# PCI_short_card_universal_-_32_BIT-5.net
KiCad netlist of a schematic drawn in Altium Designer
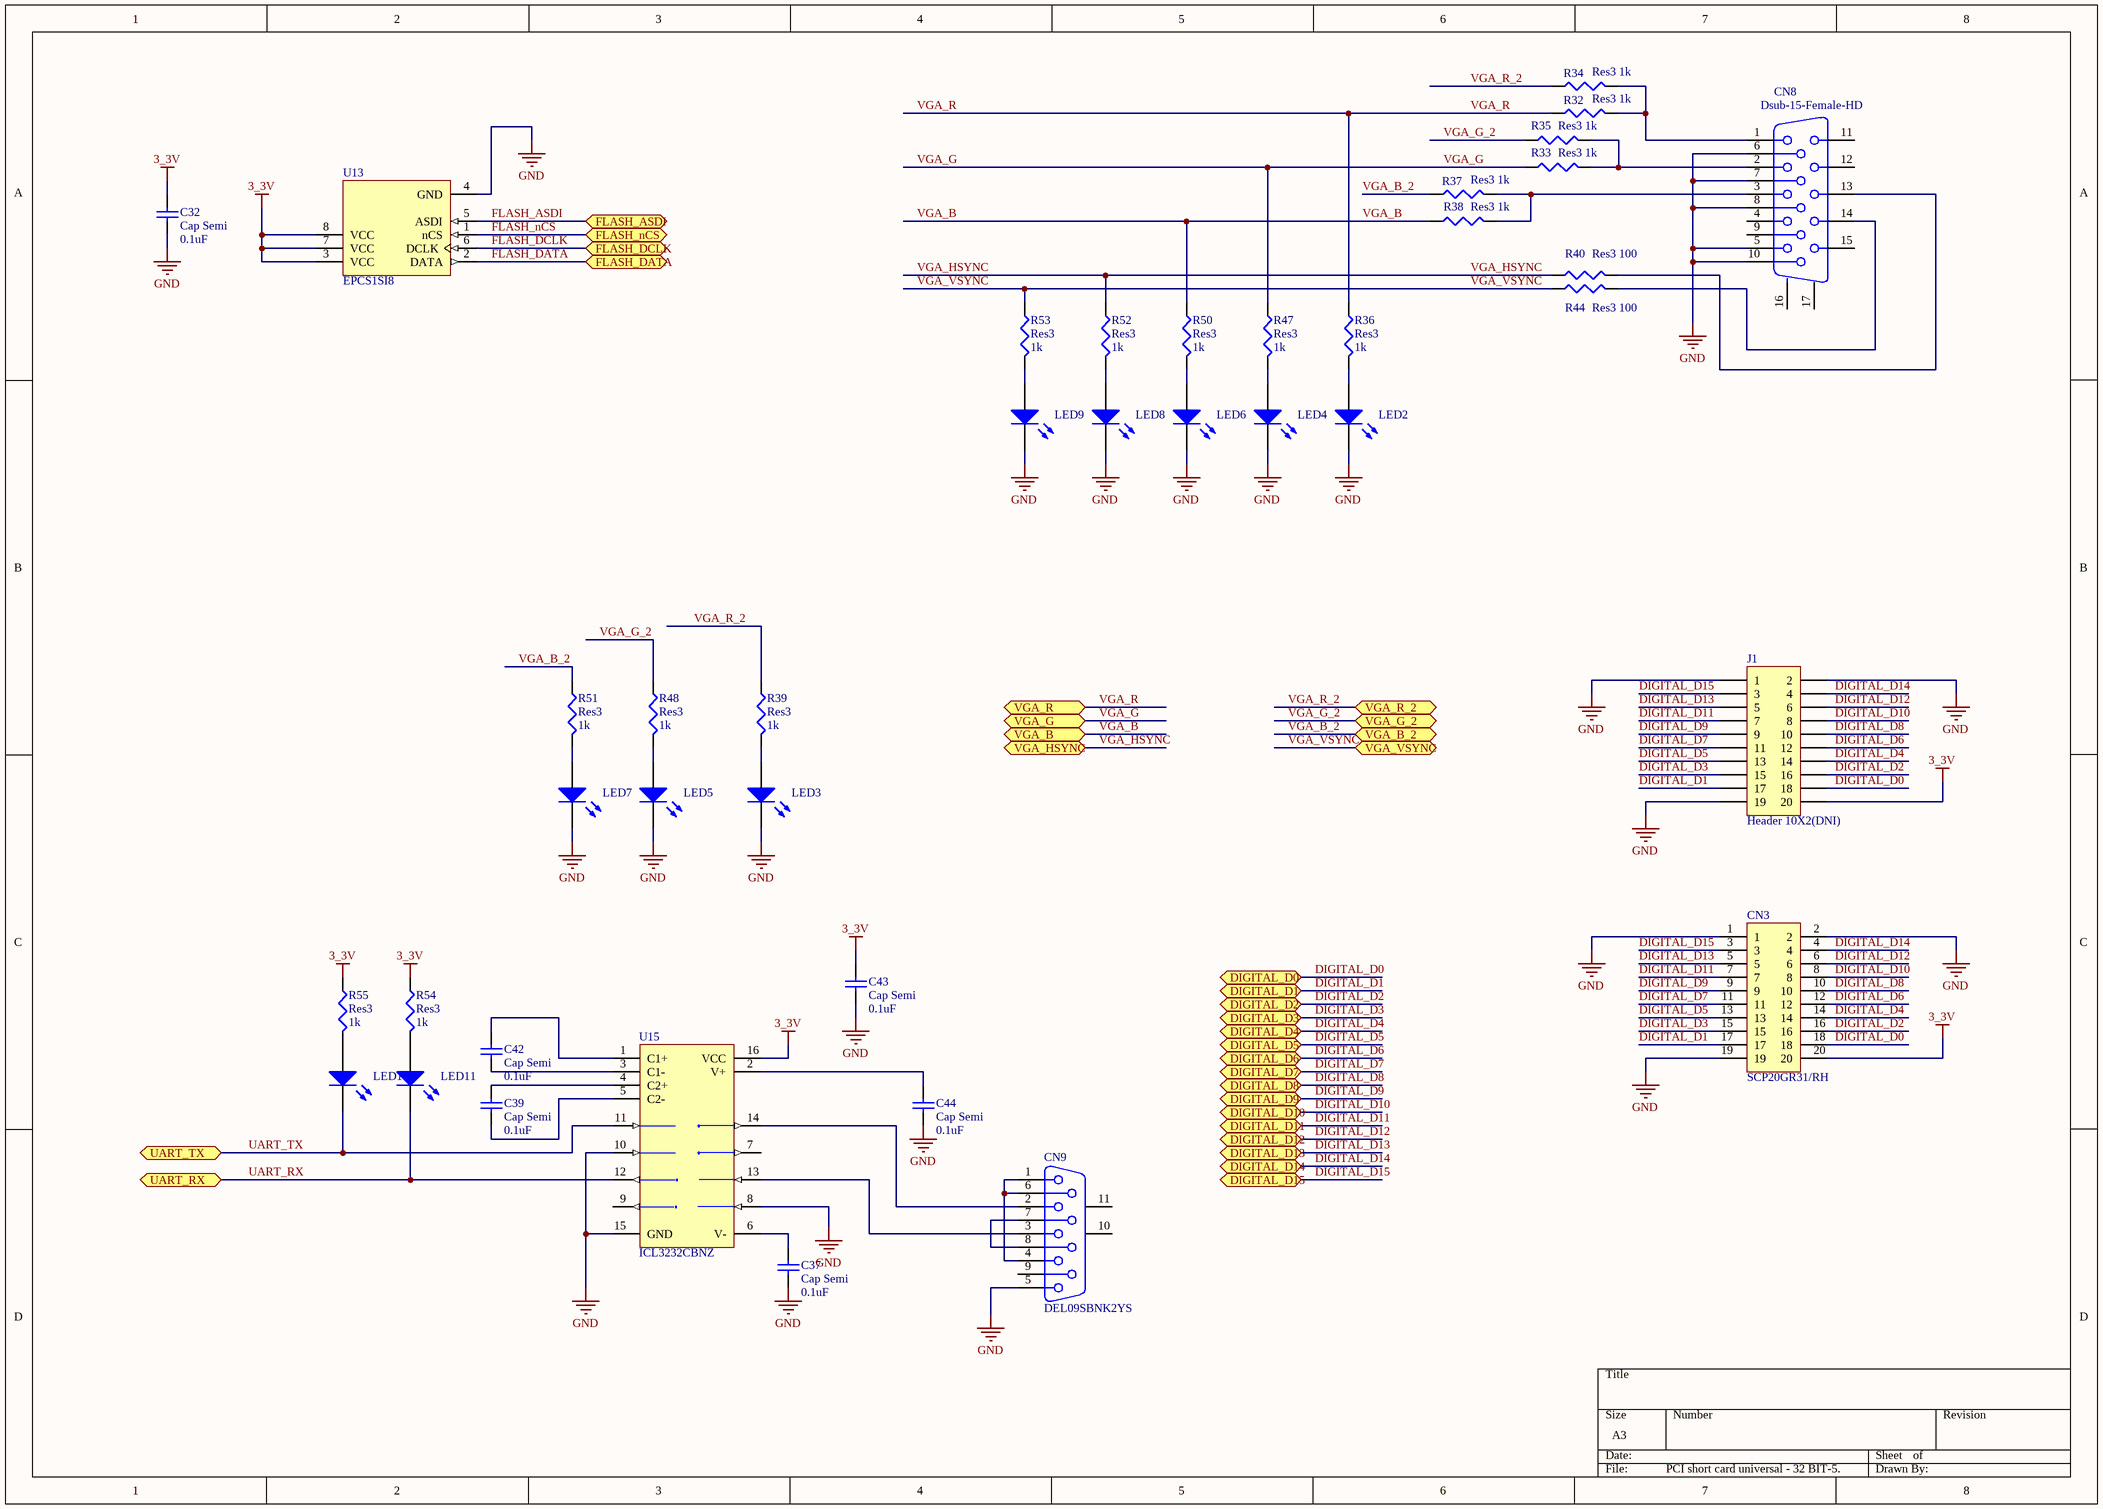
[diagram p0: PCI short card universal - 32 BIT-5.schdoc]

(export (version "E")
  (design (tool "Eeschema 10.0.6"))
  (components
    (comp (ref "C32")
      (value "Cap Semi")
      (footprint "RESC1608N")
      (description "Capacitor (Semiconductor SIM Model)")
      (fields (field (name "ALTIUM_VALUE") "0.1uF") (field (name "PUBLISHER") "Altium Limited"))
      (libsource (lib "Miscellaneous Devices") (part "Cap Semi"))
    )
    (comp (ref "C37")
      (value "Cap Semi")
      (footprint "RESC1608N")
      (description "Capacitor (Semiconductor SIM Model)")
      (fields (field (name "ALTIUM_VALUE") "0.1uF") (field (name "PUBLISHER") "Altium Limited"))
      (libsource (lib "Miscellaneous Devices") (part "Cap Semi"))
    )
    (comp (ref "C39")
      (value "Cap Semi")
      (footprint "RESC1608N")
      (description "Capacitor (Semiconductor SIM Model)")
      (fields (field (name "ALTIUM_VALUE") "0.1uF") (field (name "PUBLISHER") "Altium Limited"))
      (libsource (lib "Miscellaneous Devices") (part "Cap Semi"))
    )
    (comp (ref "C42")
      (value "Cap Semi")
      (footprint "RESC1608N")
      (description "Capacitor (Semiconductor SIM Model)")
      (fields (field (name "ALTIUM_VALUE") "0.1uF") (field (name "PUBLISHER") "Altium Limited"))
      (libsource (lib "Miscellaneous Devices") (part "Cap Semi"))
    )
    (comp (ref "C43")
      (value "Cap Semi")
      (footprint "RESC1608N")
      (description "Capacitor (Semiconductor SIM Model)")
      (fields (field (name "ALTIUM_VALUE") "0.1uF") (field (name "PUBLISHER") "Altium Limited"))
      (libsource (lib "Miscellaneous Devices") (part "Cap Semi"))
    )
    (comp (ref "C44")
      (value "Cap Semi")
      (footprint "RESC1608N")
      (description "Capacitor (Semiconductor SIM Model)")
      (fields (field (name "ALTIUM_VALUE") "0.1uF") (field (name "PUBLISHER") "Altium Limited"))
      (libsource (lib "Miscellaneous Devices") (part "Cap Semi"))
    )
    (comp (ref "CN3")
      (value "SCP20GR31/RH")
      (footprint "SCP20GR31/RH")
      (description "GTK")
      (libsource (lib "Schlib1") (part "SCP20GR31/RH"))
    )
    (comp (ref "CN8")
      (value "Dsub-15-Female-HD")
      (footprint "MyPCBLib:DB15-VGA-Female")
      (description "Dsub-15 High density VGA Female connetor")
      (fields (field (name "MANUFACTURER") "Generic Components") (field (name "PUBLISHER") "Altium Limited"))
      (libsource (lib "Altium Nanoboard Project") (part "Dsub-15-Female-HD"))
    )
    (comp (ref "CN9")
      (value "DEL09SBNK2YS")
      (footprint "DSUB1.385-2H9")
      (description "GTK")
      (fields (field (name "PUBLISHER") "Altium Limited"))
      (libsource (lib "Miscellaneous Connectors") (part "D Connector 9"))
    )
    (comp (ref "J1")
      (value "Header 10X2(DNI)")
      (footprint "HDR2X10")
      (description "Header, 10-Pin, Dual row")
      (fields (field (name "PUBLISHER") "Altium Limited"))
      (libsource (lib "Miscellaneous Connectors") (part "Header 10X2"))
    )
    (comp (ref "LED2")
      (value "LED2")
      (footprint "LED3.2X1.6X1.1")
      (description "OASISTEK (TO-3216BC-MAE)")
      (fields (field (name "PUBLISHER") "Altium Limited"))
      (libsource (lib "Miscellaneous Devices") (part "LED2"))
    )
    (comp (ref "LED3")
      (value "LED2")
      (footprint "LED3.2X1.6X1.1")
      (description "OASISTEK (TO-3216BC-MAE)")
      (fields (field (name "PUBLISHER") "Altium Limited"))
      (libsource (lib "Miscellaneous Devices") (part "LED2"))
    )
    (comp (ref "LED4")
      (value "LED2")
      (footprint "LED3.2X1.6X1.1")
      (description "OASISTEK (TO-3216BC-MAE)")
      (fields (field (name "PUBLISHER") "Altium Limited"))
      (libsource (lib "Miscellaneous Devices") (part "LED2"))
    )
    (comp (ref "LED5")
      (value "LED2")
      (footprint "LED3.2X1.6X1.1")
      (description "OASISTEK (TO-3216BC-MAE)")
      (fields (field (name "PUBLISHER") "Altium Limited"))
      (libsource (lib "Miscellaneous Devices") (part "LED2"))
    )
    (comp (ref "LED6")
      (value "LED2")
      (footprint "LED3.2X1.6X1.1")
      (description "OASISTEK (TO-3216BC-MAE)")
      (fields (field (name "PUBLISHER") "Altium Limited"))
      (libsource (lib "Miscellaneous Devices") (part "LED2"))
    )
    (comp (ref "LED7")
      (value "LED2")
      (footprint "LED3.2X1.6X1.1")
      (description "OASISTEK (TO-3216BC-MAE)")
      (fields (field (name "PUBLISHER") "Altium Limited"))
      (libsource (lib "Miscellaneous Devices") (part "LED2"))
    )
    (comp (ref "LED8")
      (value "LED2")
      (footprint "LED3.2X1.6X1.1")
      (description "OASISTEK (TO-3216BC-MAE)")
      (fields (field (name "PUBLISHER") "Altium Limited"))
      (libsource (lib "Miscellaneous Devices") (part "LED2"))
    )
    (comp (ref "LED9")
      (value "LED2")
      (footprint "LED3.2X1.6X1.1")
      (description "OASISTEK (TO-3216BC-MAE)")
      (fields (field (name "PUBLISHER") "Altium Limited"))
      (libsource (lib "Miscellaneous Devices") (part "LED2"))
    )
    (comp (ref "LED10")
      (value "LED2")
      (footprint "LED3.2X1.6X1.1")
      (description "Typical RED, GREEN, YELLOW, AMBER GaAs LED")
      (fields (field (name "PUBLISHER") "Altium Limited"))
      (libsource (lib "Miscellaneous Devices") (part "LED2"))
    )
    (comp (ref "LED11")
      (value "LED2")
      (footprint "LED3.2X1.6X1.1")
      (description "Typical RED, GREEN, YELLOW, AMBER GaAs LED")
      (fields (field (name "PUBLISHER") "Altium Limited"))
      (libsource (lib "Miscellaneous Devices") (part "LED2"))
    )
    (comp (ref "R32")
      (value "Res3")
      (footprint "RESC1608N")
      (description "Resistor")
      (fields (field (name "ALTIUM_VALUE") "1k") (field (name "PUBLISHER") "Altium Limited"))
      (libsource (lib "Miscellaneous Devices") (part "Res3"))
    )
    (comp (ref "R33")
      (value "Res3")
      (footprint "RESC1608N")
      (description "Resistor")
      (fields (field (name "ALTIUM_VALUE") "1k") (field (name "PUBLISHER") "Altium Limited"))
      (libsource (lib "Miscellaneous Devices") (part "Res3"))
    )
    (comp (ref "R34")
      (value "Res3")
      (footprint "RESC1608N")
      (description "Resistor")
      (fields (field (name "ALTIUM_VALUE") "1k") (field (name "PUBLISHER") "Altium Limited"))
      (libsource (lib "Miscellaneous Devices") (part "Res3"))
    )
    (comp (ref "R35")
      (value "Res3")
      (footprint "RESC1608N")
      (description "Resistor")
      (fields (field (name "ALTIUM_VALUE") "1k") (field (name "PUBLISHER") "Altium Limited"))
      (libsource (lib "Miscellaneous Devices") (part "Res3"))
    )
    (comp (ref "R36")
      (value "Res3")
      (footprint "RESC1608N")
      (description "Resistor")
      (fields (field (name "ALTIUM_VALUE") "1k") (field (name "PUBLISHER") "Altium Limited"))
      (libsource (lib "Miscellaneous Devices") (part "Res3"))
    )
    (comp (ref "R37")
      (value "Res3")
      (footprint "RESC1608N")
      (description "Resistor")
      (fields (field (name "ALTIUM_VALUE") "1k") (field (name "PUBLISHER") "Altium Limited"))
      (libsource (lib "Miscellaneous Devices") (part "Res3"))
    )
    (comp (ref "R38")
      (value "Res3")
      (footprint "RESC1608N")
      (description "Resistor")
      (fields (field (name "ALTIUM_VALUE") "1k") (field (name "PUBLISHER") "Altium Limited"))
      (libsource (lib "Miscellaneous Devices") (part "Res3"))
    )
    (comp (ref "R39")
      (value "Res3")
      (footprint "RESC1608N")
      (description "Resistor")
      (fields (field (name "ALTIUM_VALUE") "1k") (field (name "PUBLISHER") "Altium Limited"))
      (libsource (lib "Miscellaneous Devices") (part "Res3"))
    )
    (comp (ref "R40")
      (value "Res3")
      (footprint "RESC1608N")
      (description "Resistor")
      (fields (field (name "ALTIUM_VALUE") "100") (field (name "PUBLISHER") "Altium Limited"))
      (libsource (lib "Miscellaneous Devices") (part "Res3"))
    )
    (comp (ref "R44")
      (value "Res3")
      (footprint "RESC1608N")
      (description "Resistor")
      (fields (field (name "ALTIUM_VALUE") "100") (field (name "PUBLISHER") "Altium Limited"))
      (libsource (lib "Miscellaneous Devices") (part "Res3"))
    )
    (comp (ref "R47")
      (value "Res3")
      (footprint "RESC1608N")
      (description "Resistor")
      (fields (field (name "ALTIUM_VALUE") "1k") (field (name "PUBLISHER") "Altium Limited"))
      (libsource (lib "Miscellaneous Devices") (part "Res3"))
    )
    (comp (ref "R48")
      (value "Res3")
      (footprint "RESC1608N")
      (description "Resistor")
      (fields (field (name "ALTIUM_VALUE") "1k") (field (name "PUBLISHER") "Altium Limited"))
      (libsource (lib "Miscellaneous Devices") (part "Res3"))
    )
    (comp (ref "R50")
      (value "Res3")
      (footprint "RESC1608N")
      (description "Resistor")
      (fields (field (name "ALTIUM_VALUE") "1k") (field (name "PUBLISHER") "Altium Limited"))
      (libsource (lib "Miscellaneous Devices") (part "Res3"))
    )
    (comp (ref "R51")
      (value "Res3")
      (footprint "RESC1608N")
      (description "Resistor")
      (fields (field (name "ALTIUM_VALUE") "1k") (field (name "PUBLISHER") "Altium Limited"))
      (libsource (lib "Miscellaneous Devices") (part "Res3"))
    )
    (comp (ref "R52")
      (value "Res3")
      (footprint "RESC1608N")
      (description "Resistor")
      (fields (field (name "ALTIUM_VALUE") "1k") (field (name "PUBLISHER") "Altium Limited"))
      (libsource (lib "Miscellaneous Devices") (part "Res3"))
    )
    (comp (ref "R53")
      (value "Res3")
      (footprint "RESC1608N")
      (description "Resistor")
      (fields (field (name "ALTIUM_VALUE") "1k") (field (name "PUBLISHER") "Altium Limited"))
      (libsource (lib "Miscellaneous Devices") (part "Res3"))
    )
    (comp (ref "R54")
      (value "Res3")
      (footprint "RESC1608N")
      (description "Resistor")
      (fields (field (name "ALTIUM_VALUE") "1k") (field (name "PUBLISHER") "Altium Limited"))
      (libsource (lib "Miscellaneous Devices") (part "Res3"))
    )
    (comp (ref "R55")
      (value "Res3")
      (footprint "RESC1608N")
      (description "Resistor")
      (fields (field (name "ALTIUM_VALUE") "1k") (field (name "PUBLISHER") "Altium Limited"))
      (libsource (lib "Miscellaneous Devices") (part "Res3"))
    )
    (comp (ref "U13")
      (value "EPCS1SI8")
      (footprint "SOIC8_L")
      (fields (field (name "PUBLISHER") "Altium Limited"))
      (libsource (lib "Altera EPCS Configuration Device") (part "EPCS1SI8"))
    )
    (comp (ref "U15")
      (value "ICL3232CBNZ")
      (footprint "NSO16_M")
      (description "INTERSIL")
      (fields (field (name "PUBLISHER") "Altium Limited"))
      (libsource (lib "Maxim Communication Transceiver") (part "MAX3232CSE"))
    )
  )
  (nets
    (net (code "1") (name "/DIGITAL_D0") (class "Default")
      (node (ref "CN3") (pin "18") (pinfunction "18_18") (pintype "passive"))
      (node (ref "J1") (pin "18") (pinfunction "18_18") (pintype "passive"))
    )
    (net (code "2") (name "/DIGITAL_D1") (class "Default")
      (node (ref "CN3") (pin "17") (pinfunction "17_17") (pintype "passive"))
      (node (ref "J1") (pin "17") (pinfunction "17_17") (pintype "passive"))
    )
    (net (code "3") (name "/DIGITAL_D2") (class "Default")
      (node (ref "CN3") (pin "16") (pinfunction "16_16") (pintype "passive"))
      (node (ref "J1") (pin "16") (pinfunction "16_16") (pintype "passive"))
    )
    (net (code "4") (name "/DIGITAL_D3") (class "Default")
      (node (ref "CN3") (pin "15") (pinfunction "15_15") (pintype "passive"))
      (node (ref "J1") (pin "15") (pinfunction "15_15") (pintype "passive"))
    )
    (net (code "5") (name "/DIGITAL_D4") (class "Default")
      (node (ref "CN3") (pin "14") (pinfunction "14_14") (pintype "passive"))
      (node (ref "J1") (pin "14") (pinfunction "14_14") (pintype "passive"))
    )
    (net (code "6") (name "/DIGITAL_D5") (class "Default")
      (node (ref "CN3") (pin "13") (pinfunction "13_13") (pintype "passive"))
      (node (ref "J1") (pin "13") (pinfunction "13_13") (pintype "passive"))
    )
    (net (code "7") (name "/DIGITAL_D6") (class "Default")
      (node (ref "CN3") (pin "12") (pinfunction "12_12") (pintype "passive"))
      (node (ref "J1") (pin "12") (pinfunction "12_12") (pintype "passive"))
    )
    (net (code "8") (name "/DIGITAL_D7") (class "Default")
      (node (ref "CN3") (pin "11") (pinfunction "11_11") (pintype "passive"))
      (node (ref "J1") (pin "11") (pinfunction "11_11") (pintype "passive"))
    )
    (net (code "9") (name "/DIGITAL_D8") (class "Default")
      (node (ref "CN3") (pin "10") (pinfunction "10_10") (pintype "passive"))
      (node (ref "J1") (pin "10") (pinfunction "10_10") (pintype "passive"))
    )
    (net (code "10") (name "/DIGITAL_D9") (class "Default")
      (node (ref "CN3") (pin "9") (pinfunction "9_9") (pintype "passive"))
      (node (ref "J1") (pin "9") (pinfunction "9_9") (pintype "passive"))
    )
    (net (code "11") (name "/DIGITAL_D10") (class "Default")
      (node (ref "CN3") (pin "8") (pinfunction "8_8") (pintype "passive"))
      (node (ref "J1") (pin "8") (pinfunction "8_8") (pintype "passive"))
    )
    (net (code "12") (name "/DIGITAL_D11") (class "Default")
      (node (ref "CN3") (pin "7") (pinfunction "7_7") (pintype "passive"))
      (node (ref "J1") (pin "7") (pinfunction "7_7") (pintype "passive"))
    )
    (net (code "13") (name "/DIGITAL_D12") (class "Default")
      (node (ref "CN3") (pin "6") (pinfunction "6_6") (pintype "passive"))
      (node (ref "J1") (pin "6") (pinfunction "6_6") (pintype "passive"))
    )
    (net (code "14") (name "/DIGITAL_D13") (class "Default")
      (node (ref "CN3") (pin "5") (pinfunction "5_5") (pintype "passive"))
      (node (ref "J1") (pin "5") (pinfunction "5_5") (pintype "passive"))
    )
    (net (code "15") (name "/DIGITAL_D14") (class "Default")
      (node (ref "CN3") (pin "4") (pinfunction "4_4") (pintype "passive"))
      (node (ref "J1") (pin "4") (pinfunction "4_4") (pintype "passive"))
    )
    (net (code "16") (name "/DIGITAL_D15") (class "Default")
      (node (ref "CN3") (pin "3") (pinfunction "3_3") (pintype "passive"))
      (node (ref "J1") (pin "3") (pinfunction "3_3") (pintype "passive"))
    )
    (net (code "17") (name "/FLASH_ASDI") (class "Default")
      (node (ref "U13") (pin "5") (pinfunction "ASDI_5") (pintype "input"))
    )
    (net (code "18") (name "/FLASH_DATA") (class "Default")
      (node (ref "U13") (pin "2") (pinfunction "DATA_2") (pintype "output"))
    )
    (net (code "19") (name "/FLASH_DCLK") (class "Default")
      (node (ref "U13") (pin "6") (pinfunction "DCLK_6") (pintype "input"))
    )
    (net (code "20") (name "/FLASH_nCS") (class "Default")
      (node (ref "U13") (pin "1") (pinfunction "nCS_1") (pintype "input"))
    )
    (net (code "21") (name "/UART_RX") (class "Default")
      (node (ref "LED11") (pin "2") (pinfunction "K_2") (pintype "passive"))
      (node (ref "U15") (pin "12") (pinfunction "R1OUT_12") (pintype "output"))
    )
    (net (code "22") (name "/UART_TX") (class "Default")
      (node (ref "LED10") (pin "2") (pinfunction "K_2") (pintype "passive"))
      (node (ref "U15") (pin "11") (pinfunction "T1IN_11") (pintype "input"))
    )
    (net (code "23") (name "/VGA_B") (class "Default")
      (node (ref "R38") (pin "1") (pinfunction "1_1") (pintype "passive"))
      (node (ref "R50") (pin "1") (pinfunction "1_1") (pintype "passive"))
    )
    (net (code "24") (name "/VGA_B_2") (class "Default")
      (node (ref "R37") (pin "1") (pinfunction "1_1") (pintype "passive"))
      (node (ref "R51") (pin "1") (pinfunction "1_1") (pintype "passive"))
    )
    (net (code "25") (name "/VGA_G") (class "Default")
      (node (ref "R33") (pin "1") (pinfunction "1_1") (pintype "passive"))
      (node (ref "R47") (pin "1") (pinfunction "1_1") (pintype "passive"))
    )
    (net (code "26") (name "/VGA_G_2") (class "Default")
      (node (ref "R35") (pin "1") (pinfunction "1_1") (pintype "passive"))
      (node (ref "R48") (pin "1") (pinfunction "1_1") (pintype "passive"))
    )
    (net (code "27") (name "/VGA_HSYNC") (class "Default")
      (node (ref "R40") (pin "1") (pinfunction "1_1") (pintype "passive"))
      (node (ref "R52") (pin "1") (pinfunction "1_1") (pintype "passive"))
    )
    (net (code "28") (name "/VGA_R") (class "Default")
      (node (ref "R32") (pin "1") (pinfunction "1_1") (pintype "passive"))
      (node (ref "R36") (pin "1") (pinfunction "1_1") (pintype "passive"))
    )
    (net (code "29") (name "/VGA_R_2") (class "Default")
      (node (ref "R34") (pin "1") (pinfunction "1_1") (pintype "passive"))
      (node (ref "R39") (pin "1") (pinfunction "1_1") (pintype "passive"))
    )
    (net (code "30") (name "/VGA_VSYNC") (class "Default")
      (node (ref "R44") (pin "1") (pinfunction "1_1") (pintype "passive"))
      (node (ref "R53") (pin "1") (pinfunction "1_1") (pintype "passive"))
    )
    (net (code "31") (name "3_3V") (class "Default")
      (node (ref "C32") (pin "2") (pinfunction "2_2") (pintype "passive"))
      (node (ref "C43") (pin "2") (pinfunction "2_2") (pintype "passive"))
      (node (ref "CN3") (pin "20") (pinfunction "20_20") (pintype "passive"))
      (node (ref "J1") (pin "20") (pinfunction "20_20") (pintype "passive"))
      (node (ref "R54") (pin "1") (pinfunction "1_1") (pintype "passive"))
      (node (ref "R55") (pin "1") (pinfunction "1_1") (pintype "passive"))
      (node (ref "U13") (pin "3") (pinfunction "VCC_3") (pintype "power_in"))
      (node (ref "U13") (pin "7") (pinfunction "VCC_7") (pintype "power_in"))
      (node (ref "U13") (pin "8") (pinfunction "VCC_8") (pintype "power_in"))
      (node (ref "U15") (pin "16") (pinfunction "VCC_16") (pintype "power_in"))
    )
    (net (code "32") (name "GND") (class "Default")
      (node (ref "C32") (pin "1") (pinfunction "1_1") (pintype "passive"))
      (node (ref "C37") (pin "1") (pinfunction "1_1") (pintype "passive"))
      (node (ref "C43") (pin "1") (pinfunction "1_1") (pintype "passive"))
      (node (ref "C44") (pin "1") (pinfunction "1_1") (pintype "passive"))
      (node (ref "CN3") (pin "1") (pinfunction "1_1") (pintype "passive"))
      (node (ref "CN3") (pin "19") (pinfunction "19_19") (pintype "passive"))
      (node (ref "CN3") (pin "2") (pinfunction "2_2") (pintype "passive"))
      (node (ref "CN8") (pin "10") (pinfunction "10_10") (pintype "power_in"))
      (node (ref "CN8") (pin "5") (pinfunction "5_5") (pintype "power_in"))
      (node (ref "CN8") (pin "6") (pinfunction "6_6") (pintype "power_in"))
      (node (ref "CN8") (pin "7") (pinfunction "7_7") (pintype "power_in"))
      (node (ref "CN8") (pin "8") (pinfunction "8_8") (pintype "power_in"))
      (node (ref "CN9") (pin "5") (pinfunction "5_5") (pintype "passive"))
      (node (ref "J1") (pin "1") (pinfunction "1_1") (pintype "passive"))
      (node (ref "J1") (pin "19") (pinfunction "19_19") (pintype "passive"))
      (node (ref "J1") (pin "2") (pinfunction "2_2") (pintype "passive"))
      (node (ref "LED2") (pin "2") (pinfunction "K_2") (pintype "passive"))
      (node (ref "LED3") (pin "2") (pinfunction "K_2") (pintype "passive"))
      (node (ref "LED4") (pin "2") (pinfunction "K_2") (pintype "passive"))
      (node (ref "LED5") (pin "2") (pinfunction "K_2") (pintype "passive"))
      (node (ref "LED6") (pin "2") (pinfunction "K_2") (pintype "passive"))
      (node (ref "LED7") (pin "2") (pinfunction "K_2") (pintype "passive"))
      (node (ref "LED8") (pin "2") (pinfunction "K_2") (pintype "passive"))
      (node (ref "LED9") (pin "2") (pinfunction "K_2") (pintype "passive"))
      (node (ref "U13") (pin "4") (pinfunction "GND_4") (pintype "power_in"))
      (node (ref "U15") (pin "10") (pinfunction "T2IN_10") (pintype "input"))
      (node (ref "U15") (pin "15") (pinfunction "GND_15") (pintype "power_in"))
      (node (ref "U15") (pin "8") (pinfunction "R2IN_8") (pintype "input"))
    )
    (net (code "33") (name "Net-(CN8-Pad1)") (class "Default")
      (node (ref "CN8") (pin "1") (pinfunction "1_1") (pintype "passive"))
      (node (ref "R32") (pin "2") (pinfunction "2_2") (pintype "passive"))
      (node (ref "R34") (pin "2") (pinfunction "2_2") (pintype "passive"))
    )
    (net (code "34") (name "Net-(CN8-Pad2)") (class "Default")
      (node (ref "CN8") (pin "2") (pinfunction "2_2") (pintype "passive"))
      (node (ref "R33") (pin "2") (pinfunction "2_2") (pintype "passive"))
      (node (ref "R35") (pin "2") (pinfunction "2_2") (pintype "passive"))
    )
    (net (code "35") (name "Net-(CN8-Pad3)") (class "Default")
      (node (ref "CN8") (pin "3") (pinfunction "3_3") (pintype "passive"))
      (node (ref "R37") (pin "2") (pinfunction "2_2") (pintype "passive"))
      (node (ref "R38") (pin "2") (pinfunction "2_2") (pintype "passive"))
    )
    (net (code "36") (name "Net-(CN8-Pad13)") (class "Default")
      (node (ref "CN8") (pin "13") (pinfunction "13_13") (pintype "passive"))
      (node (ref "R40") (pin "2") (pinfunction "2_2") (pintype "passive"))
    )
    (net (code "37") (name "Net-(CN8-Pad14)") (class "Default")
      (node (ref "CN8") (pin "14") (pinfunction "14_14") (pintype "passive"))
      (node (ref "R44") (pin "2") (pinfunction "2_2") (pintype "passive"))
    )
    (net (code "38") (name "Net-(CN9-Pad1)") (class "Default")
      (node (ref "CN9") (pin "1") (pinfunction "1_1") (pintype "passive"))
      (node (ref "CN9") (pin "4") (pinfunction "4_4") (pintype "passive"))
      (node (ref "CN9") (pin "6") (pinfunction "6_6") (pintype "passive"))
    )
    (net (code "39") (name "Net-(CN9-Pad7)") (class "Default")
      (node (ref "CN9") (pin "7") (pinfunction "7_7") (pintype "passive"))
      (node (ref "CN9") (pin "8") (pinfunction "8_8") (pintype "passive"))
    )
    (net (code "40") (name "Net-(LED2-A)") (class "Default")
      (node (ref "LED2") (pin "1") (pinfunction "A_1") (pintype "passive"))
      (node (ref "R36") (pin "2") (pinfunction "2_2") (pintype "passive"))
    )
    (net (code "41") (name "Net-(LED3-A)") (class "Default")
      (node (ref "LED3") (pin "1") (pinfunction "A_1") (pintype "passive"))
      (node (ref "R39") (pin "2") (pinfunction "2_2") (pintype "passive"))
    )
    (net (code "42") (name "Net-(LED4-A)") (class "Default")
      (node (ref "LED4") (pin "1") (pinfunction "A_1") (pintype "passive"))
      (node (ref "R47") (pin "2") (pinfunction "2_2") (pintype "passive"))
    )
    (net (code "43") (name "Net-(LED5-A)") (class "Default")
      (node (ref "LED5") (pin "1") (pinfunction "A_1") (pintype "passive"))
      (node (ref "R48") (pin "2") (pinfunction "2_2") (pintype "passive"))
    )
    (net (code "44") (name "Net-(LED6-A)") (class "Default")
      (node (ref "LED6") (pin "1") (pinfunction "A_1") (pintype "passive"))
      (node (ref "R50") (pin "2") (pinfunction "2_2") (pintype "passive"))
    )
    (net (code "45") (name "Net-(LED7-A)") (class "Default")
      (node (ref "LED7") (pin "1") (pinfunction "A_1") (pintype "passive"))
      (node (ref "R51") (pin "2") (pinfunction "2_2") (pintype "passive"))
    )
    (net (code "46") (name "Net-(LED8-A)") (class "Default")
      (node (ref "LED8") (pin "1") (pinfunction "A_1") (pintype "passive"))
      (node (ref "R52") (pin "2") (pinfunction "2_2") (pintype "passive"))
    )
    (net (code "47") (name "Net-(LED9-A)") (class "Default")
      (node (ref "LED9") (pin "1") (pinfunction "A_1") (pintype "passive"))
      (node (ref "R53") (pin "2") (pinfunction "2_2") (pintype "passive"))
    )
    (net (code "48") (name "Net-(LED10-A)") (class "Default")
      (node (ref "LED10") (pin "1") (pinfunction "A_1") (pintype "passive"))
      (node (ref "R55") (pin "2") (pinfunction "2_2") (pintype "passive"))
    )
    (net (code "49") (name "Net-(LED11-A)") (class "Default")
      (node (ref "LED11") (pin "1") (pinfunction "A_1") (pintype "passive"))
      (node (ref "R54") (pin "2") (pinfunction "2_2") (pintype "passive"))
    )
    (net (code "50") (name "Net-(U15-C1+)") (class "Default")
      (node (ref "C42") (pin "2") (pinfunction "2_2") (pintype "passive"))
      (node (ref "U15") (pin "1") (pinfunction "C1+_1") (pintype "passive"))
    )
    (net (code "51") (name "Net-(U15-C1-)") (class "Default")
      (node (ref "C42") (pin "1") (pinfunction "1_1") (pintype "passive"))
      (node (ref "U15") (pin "3") (pinfunction "C1-_3") (pintype "passive"))
    )
    (net (code "52") (name "Net-(U15-C2+)") (class "Default")
      (node (ref "C39") (pin "2") (pinfunction "2_2") (pintype "passive"))
      (node (ref "U15") (pin "4") (pinfunction "C2+_4") (pintype "passive"))
    )
    (net (code "53") (name "Net-(U15-C2-)") (class "Default")
      (node (ref "C39") (pin "1") (pinfunction "1_1") (pintype "passive"))
      (node (ref "U15") (pin "5") (pinfunction "C2-_5") (pintype "passive"))
    )
    (net (code "54") (name "Net-(U15-R1IN)") (class "Default")
      (node (ref "CN9") (pin "3") (pinfunction "3_3") (pintype "passive"))
      (node (ref "U15") (pin "13") (pinfunction "R1IN_13") (pintype "input"))
    )
    (net (code "55") (name "Net-(U15-T1OUT)") (class "Default")
      (node (ref "CN9") (pin "2") (pinfunction "2_2") (pintype "passive"))
      (node (ref "U15") (pin "14") (pinfunction "T1OUT_14") (pintype "output"))
    )
    (net (code "56") (name "Net-(U15-V+)") (class "Default")
      (node (ref "C44") (pin "2") (pinfunction "2_2") (pintype "passive"))
      (node (ref "U15") (pin "2") (pinfunction "V+_2") (pintype "power_in"))
    )
    (net (code "57") (name "Net-(U15-V-)") (class "Default")
      (node (ref "C37") (pin "2") (pinfunction "2_2") (pintype "passive"))
      (node (ref "U15") (pin "6") (pinfunction "V-_6") (pintype "power_in"))
    )
    (net (code "58") (name "unconnected-(CN8-MH1-Pad16)") (class "Default")
      (node (ref "CN8") (pin "16") (pinfunction "MH1_16") (pintype "passive"))
    )
    (net (code "59") (name "unconnected-(CN8-MH2-Pad17)") (class "Default")
      (node (ref "CN8") (pin "17") (pinfunction "MH2_17") (pintype "passive"))
    )
    (net (code "60") (name "unconnected-(CN8-Pad4)") (class "Default")
      (node (ref "CN8") (pin "4") (pinfunction "4_4") (pintype "passive"))
    )
    (net (code "61") (name "unconnected-(CN8-Pad9)") (class "Default")
      (node (ref "CN8") (pin "9") (pinfunction "9_9") (pintype "passive"))
    )
    (net (code "62") (name "unconnected-(CN8-Pad11)") (class "Default")
      (node (ref "CN8") (pin "11") (pinfunction "11_11") (pintype "power_in"))
    )
    (net (code "63") (name "unconnected-(CN8-Pad12)") (class "Default")
      (node (ref "CN8") (pin "12") (pinfunction "12_12") (pintype "passive"))
    )
    (net (code "64") (name "unconnected-(CN8-Pad15)") (class "Default")
      (node (ref "CN8") (pin "15") (pinfunction "15_15") (pintype "passive"))
    )
    (net (code "65") (name "unconnected-(CN9-MH1-Pad10)") (class "Default")
      (node (ref "CN9") (pin "10") (pinfunction "MH1_10") (pintype "passive"))
    )
    (net (code "66") (name "unconnected-(CN9-MH2-Pad11)") (class "Default")
      (node (ref "CN9") (pin "11") (pinfunction "MH2_11") (pintype "passive"))
    )
    (net (code "67") (name "unconnected-(CN9-Pad9)") (class "Default")
      (node (ref "CN9") (pin "9") (pinfunction "9_9") (pintype "passive"))
    )
    (net (code "68") (name "unconnected-(U15-R2OUT-Pad9)") (class "Default")
      (node (ref "U15") (pin "9") (pinfunction "R2OUT_9") (pintype "output"))
    )
    (net (code "69") (name "unconnected-(U15-T2OUT-Pad7)") (class "Default")
      (node (ref "U15") (pin "7") (pinfunction "T2OUT_7") (pintype "output"))
    )
  )
)
